# SCH_SHT30.net
KiCad netlist of a schematic drawn in Altium Designer
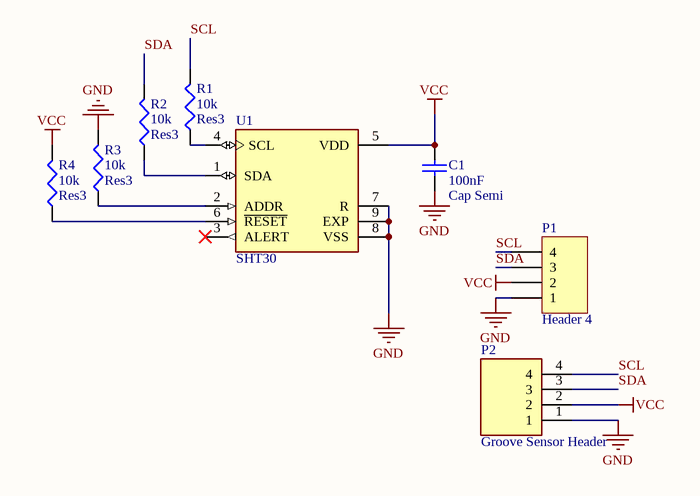
[diagram p0: SCH_SHT30.SchDoc]

(export (version "E")
  (design (tool "Eeschema 10.0.6"))
  (components
    (comp (ref "C1")
      (value "Cap Semi")
      (footprint "1608[0603]")
      (description "Capacitor (Semiconductor SIM Model)")
      (fields (field (name "ALTIUM_VALUE") "100nF") (field (name "PUBLISHER") "Altium Limited"))
      (libsource (lib "Miscellaneous Devices") (part "Cap Semi"))
    )
    (comp (ref "P1")
      (value "Header 4")
      (footprint "HDR1X4")
      (description "Header, 4-Pin")
      (fields (field (name "PUBLISHER") "Altium Limited"))
      (libsource (lib "Miscellaneous Connectors") (part "Header 4"))
    )
    (comp (ref "P2")
      (value "Groove Sensor Header")
      (footprint "SEEED_110990030")
      (description "GROVE 2MM 4PIN VERT CONN 10PCS")
      (fields (field (name "MP") "110990030") (field (name "MF") "Seeed Technology"))
      (libsource (lib "Titouan Lasquellec") (part "110990030"))
    )
    (comp (ref "R1")
      (value "Res3")
      (footprint "J1-0603")
      (description "Resistor")
      (fields (field (name "ALTIUM_VALUE") "10k") (field (name "PUBLISHER") "Altium Limited"))
      (libsource (lib "Miscellaneous Devices") (part "Res3"))
    )
    (comp (ref "R2")
      (value "Res3")
      (footprint "J1-0603")
      (description "Resistor")
      (fields (field (name "ALTIUM_VALUE") "10k") (field (name "PUBLISHER") "Altium Limited"))
      (libsource (lib "Miscellaneous Devices") (part "Res3"))
    )
    (comp (ref "R3")
      (value "Res3")
      (footprint "J1-0603")
      (description "Resistor")
      (fields (field (name "ALTIUM_VALUE") "10k") (field (name "PUBLISHER") "Altium Limited"))
      (libsource (lib "Miscellaneous Devices") (part "Res3"))
    )
    (comp (ref "R4")
      (value "Res3")
      (footprint "J1-0603")
      (description "Resistor")
      (fields (field (name "ALTIUM_VALUE") "10k") (field (name "PUBLISHER") "Altium Limited"))
      (libsource (lib "Miscellaneous Devices") (part "Res3"))
    )
    (comp (ref "U1")
      (value "SHT30")
      (footprint "XDCR_SHT30-DIS-B10KS")
      (description "SENSOR HUMID/TEMP 5V I2C 2% SMD")
      (fields (field (name "MP") "SHT30-DIS-B10KS"))
      (libsource (lib "SHT30-DIS-B10KS") (part "SHT30-DIS-B10KS"))
    )
  )
  (nets
    (net (code "1") (name "/SCL") (class "Default")
      (node (ref "P1") (pin "4") (pinfunction "4_4") (pintype "passive"))
      (node (ref "P2") (pin "4") (pinfunction "4_4") (pintype "passive"))
      (node (ref "R1") (pin "2") (pinfunction "2_2") (pintype "passive"))
    )
    (net (code "2") (name "/SDA") (class "Default")
      (node (ref "P1") (pin "3") (pinfunction "3_3") (pintype "passive"))
      (node (ref "P2") (pin "3") (pinfunction "3_3") (pintype "passive"))
      (node (ref "R2") (pin "2") (pinfunction "2_2") (pintype "passive"))
    )
    (net (code "3") (name "GND") (class "Default")
      (node (ref "C1") (pin "1") (pinfunction "1_1") (pintype "passive"))
      (node (ref "P1") (pin "1") (pinfunction "1_1") (pintype "passive"))
      (node (ref "P2") (pin "1") (pinfunction "1_1") (pintype "passive"))
      (node (ref "R3") (pin "2") (pinfunction "2_2") (pintype "passive"))
      (node (ref "U1") (pin "7") (pinfunction "R_7") (pintype "passive"))
      (node (ref "U1") (pin "8") (pinfunction "VSS_8") (pintype "power_in"))
      (node (ref "U1") (pin "9") (pinfunction "EXP_9") (pintype "passive"))
    )
    (net (code "4") (name "Net-(U1-ADDR)") (class "Default")
      (node (ref "R3") (pin "1") (pinfunction "1_1") (pintype "passive"))
      (node (ref "U1") (pin "2") (pinfunction "ADDR_2") (pintype "input"))
    )
    (net (code "5") (name "Net-(U1-SCL)") (class "Default")
      (node (ref "R1") (pin "1") (pinfunction "1_1") (pintype "passive"))
      (node (ref "U1") (pin "4") (pinfunction "SCL_4") (pintype "bidirectional"))
    )
    (net (code "6") (name "Net-(U1-SDA)") (class "Default")
      (node (ref "R2") (pin "1") (pinfunction "1_1") (pintype "passive"))
      (node (ref "U1") (pin "1") (pinfunction "SDA_1") (pintype "bidirectional"))
    )
    (net (code "7") (name "Net-(U1-~{RESET})") (class "Default")
      (node (ref "R4") (pin "1") (pinfunction "1_1") (pintype "passive"))
      (node (ref "U1") (pin "6") (pinfunction "~{RESET}_6") (pintype "input"))
    )
    (net (code "8") (name "VCC") (class "Default")
      (node (ref "C1") (pin "2") (pinfunction "2_2") (pintype "passive"))
      (node (ref "P1") (pin "2") (pinfunction "2_2") (pintype "passive"))
      (node (ref "P2") (pin "2") (pinfunction "2_2") (pintype "passive"))
      (node (ref "R4") (pin "2") (pinfunction "2_2") (pintype "passive"))
      (node (ref "U1") (pin "5") (pinfunction "VDD_5") (pintype "power_in"))
    )
    (net (code "9") (name "unconnected-(U1-ALERT-Pad3)") (class "Default")
      (node (ref "U1") (pin "3") (pinfunction "ALERT_3") (pintype "output+no_connect"))
    )
  )
)
